# relay-dpdt-motor.net
KiCad netlist of a schematic drawn in EAGLE
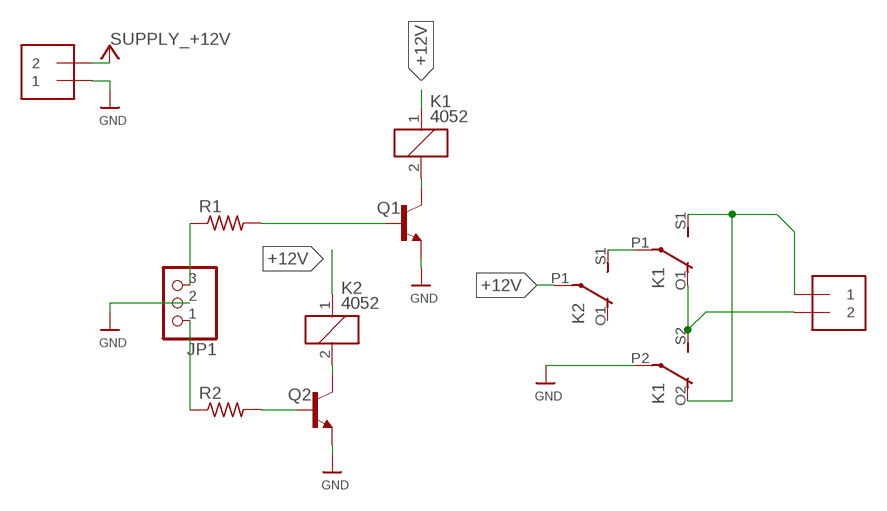
[diagram p0: schematic, sheet 1]

(export (version "E")
  (design (tool "Eeschema 10.0.6"))
  (components
    (comp (ref "J1")
      (value "1X2-3.5MM")
      (footprint "eagle-import:1X2-3.5MM")
      (libsource (lib "eagle-import") (part "1X2-3.5MM"))
    )
    (comp (ref "J2")
      (value "1X2-3.5MM")
      (footprint "eagle-import:1X2-3.5MM")
      (libsource (lib "eagle-import") (part "1X2-3.5MM"))
    )
    (comp (ref "JP1")
      (value "PINHD-1X3CB")
      (footprint "eagle-import:1X03-CLEANBIG")
      (libsource (lib "eagle-import") (part "PINHD-1X3CB"))
    )
    (comp (ref "K1")
      (value "4052")
      (footprint "eagle-import:F4052")
      (libsource (lib "eagle-import") (part "4052"))
    )
    (comp (ref "K2")
      (value "4052")
      (footprint "eagle-import:F4052")
      (libsource (lib "eagle-import") (part "4052"))
    )
    (comp (ref "Q1")
      (value "TRANSISTOR_BJT_NPN-TO-92-EBC")
      (footprint "eagle-import:TO-92")
      (libsource (lib "eagle-import") (part "TRANSISTOR_BJT_NPN-TO-92-EBC"))
    )
    (comp (ref "Q2")
      (value "TRANSISTOR_BJT_NPN-TO-92-EBC")
      (footprint "eagle-import:TO-92")
      (libsource (lib "eagle-import") (part "TRANSISTOR_BJT_NPN-TO-92-EBC"))
    )
    (comp (ref "R1")
      (value "R-US_0204/7")
      (footprint "eagle-import:0204_7")
      (libsource (lib "eagle-import") (part "R-US_0204/7"))
    )
    (comp (ref "R2")
      (value "R-US_0204/7")
      (footprint "eagle-import:0204_7")
      (libsource (lib "eagle-import") (part "R-US_0204/7"))
    )
  )
  (nets
    (net (code "1") (name "+12V") (class "Default")
      (node (ref "J1") (pin "2") (pinfunction "2_2") (pintype "passive"))
      (node (ref "K1") (pin "1") (pinfunction "1_1") (pintype "passive"))
      (node (ref "K2") (pin "1") (pinfunction "1_1") (pintype "passive"))
      (node (ref "K2") (pin "P1") (pinfunction "P_P1") (pintype "passive"))
    )
    (net (code "2") (name "GND") (class "Default")
      (node (ref "J1") (pin "1") (pinfunction "1_1") (pintype "passive"))
      (node (ref "JP1") (pin "2") (pinfunction "2_2") (pintype "passive"))
      (node (ref "K1") (pin "P2") (pinfunction "P_P2") (pintype "passive"))
      (node (ref "Q1") (pin "1") (pinfunction "E_1") (pintype "passive"))
      (node (ref "Q2") (pin "1") (pinfunction "E_1") (pintype "passive"))
    )
    (net (code "3") (name "Net-(JP1-Pad1)") (class "Default")
      (node (ref "JP1") (pin "1") (pinfunction "1_1") (pintype "passive"))
      (node (ref "R2") (pin "1") (pinfunction "1_1") (pintype "passive"))
    )
    (net (code "4") (name "Net-(JP1-Pad3)") (class "Default")
      (node (ref "JP1") (pin "3") (pinfunction "3_3") (pintype "passive"))
      (node (ref "R1") (pin "1") (pinfunction "1_1") (pintype "passive"))
    )
    (net (code "5") (name "Net-(K1B-O)") (class "Default")
      (node (ref "J2") (pin "2") (pinfunction "2_2") (pintype "passive"))
      (node (ref "K1") (pin "O1") (pinfunction "O_O1") (pintype "passive"))
      (node (ref "K1") (pin "S2") (pinfunction "S_S2") (pintype "passive"))
    )
    (net (code "6") (name "Net-(K1B-P)") (class "Default")
      (node (ref "K1") (pin "P1") (pinfunction "P_P1") (pintype "passive"))
      (node (ref "K2") (pin "S1") (pinfunction "S_S1") (pintype "passive"))
    )
    (net (code "7") (name "Net-(K1B-S)") (class "Default")
      (node (ref "J2") (pin "1") (pinfunction "1_1") (pintype "passive"))
      (node (ref "K1") (pin "O2") (pinfunction "O_O2") (pintype "passive"))
      (node (ref "K1") (pin "S1") (pinfunction "S_S1") (pintype "passive"))
    )
    (net (code "8") (name "Net-(Q1-B)") (class "Default")
      (node (ref "Q1") (pin "2") (pinfunction "B_2") (pintype "passive"))
      (node (ref "R1") (pin "2") (pinfunction "2_2") (pintype "passive"))
    )
    (net (code "9") (name "Net-(Q1-C)") (class "Default")
      (node (ref "K1") (pin "2") (pinfunction "2_2") (pintype "passive"))
      (node (ref "Q1") (pin "3") (pinfunction "C_3") (pintype "passive"))
    )
    (net (code "10") (name "Net-(Q2-B)") (class "Default")
      (node (ref "Q2") (pin "2") (pinfunction "B_2") (pintype "passive"))
      (node (ref "R2") (pin "2") (pinfunction "2_2") (pintype "passive"))
    )
    (net (code "11") (name "Net-(Q2-C)") (class "Default")
      (node (ref "K2") (pin "2") (pinfunction "2_2") (pintype "passive"))
      (node (ref "Q2") (pin "3") (pinfunction "C_3") (pintype "passive"))
    )
    (net (code "12") (name "unconnected-(K2B-O-PadO1)") (class "Default")
      (node (ref "K2") (pin "O1") (pinfunction "O_O1") (pintype "passive"))
    )
  )
)
